# Qwiic_Relay_v11.net
KiCad netlist of a schematic drawn in EAGLE
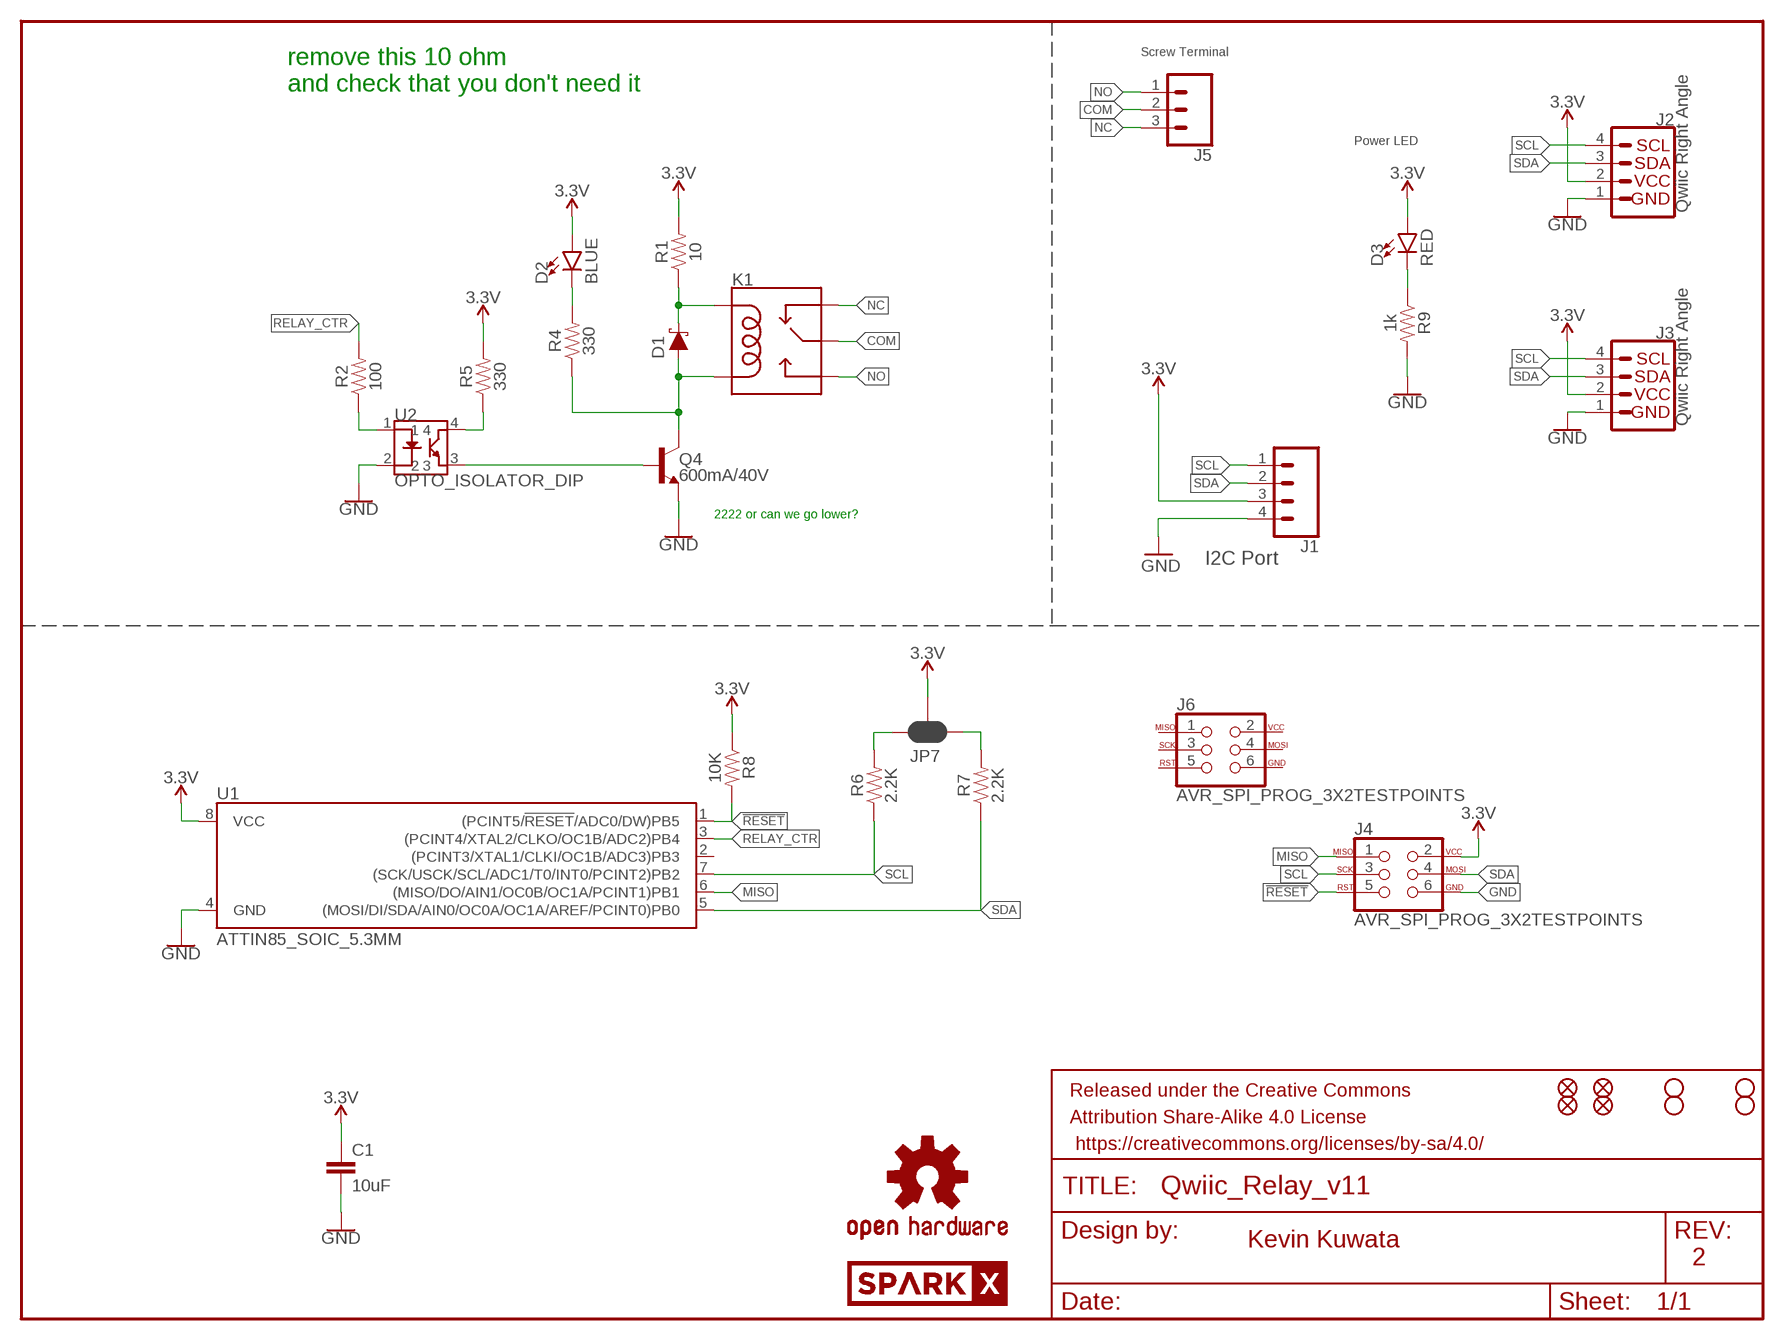
[diagram p0: schematic, sheet 1]

(export (version "E")
  (design (tool "Eeschema 10.0.6"))
  (components
    (comp (ref "C1")
      (value "10uF")
      (footprint "eagle-import:0603")
      (libsource (lib "eagle-import") (part "10UF-0603-6.3V-20%"))
    )
    (comp (ref "D1")
      (value "1A/23V/620mV")
      (footprint "eagle-import:SOD-323")
      (libsource (lib "eagle-import") (part "DIODE-SCHOTTKY-BAT20J"))
    )
    (comp (ref "D2")
      (value "BLUE")
      (footprint "eagle-import:LED-0603")
      (libsource (lib "eagle-import") (part "LED-BLUE0603"))
    )
    (comp (ref "D3")
      (value "RED")
      (footprint "eagle-import:LED-0603")
      (libsource (lib "eagle-import") (part "LED-RED0603"))
    )
    (comp (ref "FRAME1")
      (value "FRAME-LETTER")
      (footprint "eagle-import:CREATIVE_COMMONS")
      (libsource (lib "eagle-import") (part "FRAME-LETTER"))
    )
    (comp (ref "J1")
      (value "CONN_041X04_NO_SILK")
      (footprint "eagle-import:1X04_NO_SILK")
      (libsource (lib "eagle-import") (part "CONN_041X04_NO_SILK"))
    )
    (comp (ref "J2")
      (value "Qwiic Right Angle")
      (footprint "eagle-import:1X04_1MM_RA")
      (libsource (lib "eagle-import") (part "I2C_STANDARDQWIIC"))
    )
    (comp (ref "J3")
      (value "Qwiic Right Angle")
      (footprint "eagle-import:1X04_1MM_RA")
      (libsource (lib "eagle-import") (part "I2C_STANDARDQWIIC"))
    )
    (comp (ref "J4")
      (value "AVR_SPI_PROG_3X2TESTPOINTS")
      (footprint "eagle-import:2X3_TEST_POINTS")
      (libsource (lib "eagle-import") (part "AVR_SPI_PROG_3X2TESTPOINTS"))
    )
    (comp (ref "J5")
      (value "CONN_03-SCREW-5MM")
      (footprint "eagle-import:SCREWTERMINAL-5MM-3")
      (libsource (lib "eagle-import") (part "CONN_03-SCREW-5MM"))
    )
    (comp (ref "J6")
      (value "AVR_SPI_PROG_3X2TESTPOINTS")
      (footprint "eagle-import:2X3_TEST_POINTS")
      (libsource (lib "eagle-import") (part "AVR_SPI_PROG_3X2TESTPOINTS"))
    )
    (comp (ref "JP1")
      (value "STAND-OFF")
      (footprint "eagle-import:STAND-OFF")
      (libsource (lib "eagle-import") (part "STAND-OFF"))
    )
    (comp (ref "JP2")
      (value "FIDUCIALUFIDUCIAL")
      (footprint "eagle-import:MICRO-FIDUCIAL")
      (libsource (lib "eagle-import") (part "FIDUCIALUFIDUCIAL"))
    )
    (comp (ref "JP3")
      (value "STAND-OFF")
      (footprint "eagle-import:STAND-OFF")
      (libsource (lib "eagle-import") (part "STAND-OFF"))
    )
    (comp (ref "JP4")
      (value "STAND-OFF")
      (footprint "eagle-import:STAND-OFF")
      (libsource (lib "eagle-import") (part "STAND-OFF"))
    )
    (comp (ref "JP5")
      (value "STAND-OFF")
      (footprint "eagle-import:STAND-OFF")
      (libsource (lib "eagle-import") (part "STAND-OFF"))
    )
    (comp (ref "JP6")
      (value "FIDUCIALUFIDUCIAL")
      (footprint "eagle-import:MICRO-FIDUCIAL")
      (libsource (lib "eagle-import") (part "FIDUCIALUFIDUCIAL"))
    )
    (comp (ref "JP7")
      (value "JUMPER-SMT_3_2-NC_PASTE_SILK")
      (footprint "eagle-import:SMT-JUMPER_3_2-NC_PASTE_SILK")
      (libsource (lib "eagle-import") (part "JUMPER-SMT_3_2-NC_PASTE_SILK"))
    )
    (comp (ref "JP8")
      (value "FIDUCIALUFIDUCIAL")
      (footprint "eagle-import:MICRO-FIDUCIAL")
      (libsource (lib "eagle-import") (part "FIDUCIALUFIDUCIAL"))
    )
    (comp (ref "JP9")
      (value "FIDUCIALUFIDUCIAL")
      (footprint "eagle-import:MICRO-FIDUCIAL")
      (libsource (lib "eagle-import") (part "FIDUCIALUFIDUCIAL"))
    )
    (comp (ref "K1")
      (value "RELAY_SPDT_1C")
      (footprint "eagle-import:RELAY_SPDT_1C")
      (libsource (lib "eagle-import") (part "RELAY_SPDT_1C"))
    )
    (comp (ref "LOGO1")
      (value "OSHW-LOGOMINI")
      (footprint "eagle-import:OSHW-LOGO-MINI")
      (libsource (lib "eagle-import") (part "OSHW-LOGOMINI"))
    )
    (comp (ref "Q4")
      (value "600mA/40V")
      (footprint "eagle-import:SOT23-3")
      (libsource (lib "eagle-import") (part "TRANS_NPN-MMBT2222AL"))
    )
    (comp (ref "R1")
      (value "10")
      (footprint "eagle-import:0603")
      (libsource (lib "eagle-import") (part "47KOHM-0603-1/10W-1%"))
    )
    (comp (ref "R2")
      (value "100")
      (footprint "eagle-import:0603")
      (libsource (lib "eagle-import") (part "100OHM-0603-1/4W-5%"))
    )
    (comp (ref "R4")
      (value "330")
      (footprint "eagle-import:0603")
      (libsource (lib "eagle-import") (part "300OHM-0603-1/10W-1%"))
    )
    (comp (ref "R5")
      (value "330")
      (footprint "eagle-import:0603")
      (libsource (lib "eagle-import") (part "330OHM-0603-1/10W-1%"))
    )
    (comp (ref "R6")
      (value "2.2K")
      (footprint "eagle-import:0603")
      (libsource (lib "eagle-import") (part "4.7KOHM-0603-1/10W-1%"))
    )
    (comp (ref "R7")
      (value "2.2K")
      (footprint "eagle-import:0603")
      (libsource (lib "eagle-import") (part "4.7KOHM-0603-1/10W-1%"))
    )
    (comp (ref "R8")
      (value "10K")
      (footprint "eagle-import:0603")
      (libsource (lib "eagle-import") (part "330OHM-0603-1/10W-1%"))
    )
    (comp (ref "R9")
      (value "1k")
      (footprint "eagle-import:0603")
      (libsource (lib "eagle-import") (part "330OHM-0603-1/10W-1%"))
    )
    (comp (ref "U$3")
      (value "SPARKX-LOGO4")
      (footprint "eagle-import:SPARKX-MEDIUM")
      (libsource (lib "eagle-import") (part "SPARKX-LOGO4"))
    )
    (comp (ref "U$4")
      (value "SPARKX-LOGO4")
      (footprint "eagle-import:SPARKX-MEDIUM")
      (libsource (lib "eagle-import") (part "SPARKX-LOGO4"))
    )
    (comp (ref "U1")
      (value "ATTIN85_SOIC_5.3MM")
      (footprint "eagle-import:ATTINY85")
      (libsource (lib "eagle-import") (part "ATTIN85_SOIC_5.3MM"))
    )
    (comp (ref "U2")
      (value "OPTO_ISOLATOR_DIP")
      (footprint "eagle-import:4PIN_DIP")
      (libsource (lib "eagle-import") (part "OPTO_ISOLATOR_DIP"))
    )
  )
  (nets
    (net (code "1") (name "/~{RESET}") (class "Default")
      (node (ref "J4") (pin "5") (pinfunction "5_5") (pintype "passive"))
      (node (ref "R8") (pin "2") (pinfunction "2_2") (pintype "passive"))
      (node (ref "U1") (pin "1") (pinfunction "(PCINT5/~{RESET}/ADC0/DW)PB5_1") (pintype "bidirectional"))
    )
    (net (code "2") (name "3.3V") (class "Default")
      (node (ref "C1") (pin "1") (pinfunction "1_1") (pintype "passive"))
      (node (ref "D2") (pin "A") (pinfunction "A_A") (pintype "passive"))
      (node (ref "D3") (pin "A") (pinfunction "A_A") (pintype "passive"))
      (node (ref "J1") (pin "3") (pinfunction "3_3") (pintype "passive"))
      (node (ref "J2") (pin "2") (pinfunction "2_2") (pintype "power_in"))
      (node (ref "J3") (pin "2") (pinfunction "2_2") (pintype "power_in"))
      (node (ref "J4") (pin "2") (pinfunction "2_2") (pintype "passive"))
      (node (ref "JP7") (pin "2") (pinfunction "2_2") (pintype "passive"))
      (node (ref "R1") (pin "2") (pinfunction "2_2") (pintype "passive"))
      (node (ref "R5") (pin "2") (pinfunction "2_2") (pintype "passive"))
      (node (ref "R8") (pin "1") (pinfunction "1_1") (pintype "passive"))
      (node (ref "U1") (pin "8") (pinfunction "VCC_8") (pintype "bidirectional"))
    )
    (net (code "3") (name "COM") (class "Default")
      (node (ref "J5") (pin "2") (pinfunction "2_2") (pintype "passive"))
      (node (ref "K1") (pin "1") (pinfunction "MAIN_1") (pintype "bidirectional"))
    )
    (net (code "4") (name "GND") (class "Default")
      (node (ref "C1") (pin "2") (pinfunction "2_2") (pintype "passive"))
      (node (ref "J1") (pin "4") (pinfunction "4_4") (pintype "passive"))
      (node (ref "J2") (pin "1") (pinfunction "1_1") (pintype "power_in"))
      (node (ref "J3") (pin "1") (pinfunction "1_1") (pintype "power_in"))
      (node (ref "J4") (pin "6") (pinfunction "6_6") (pintype "passive"))
      (node (ref "Q4") (pin "2") (pinfunction "E_2") (pintype "passive"))
      (node (ref "R9") (pin "2") (pinfunction "2_2") (pintype "passive"))
      (node (ref "U1") (pin "4") (pinfunction "GND_4") (pintype "bidirectional"))
      (node (ref "U2") (pin "2") (pinfunction "2_2") (pintype "bidirectional"))
    )
    (net (code "5") (name "MISO") (class "Default")
      (node (ref "J4") (pin "1") (pinfunction "1_1") (pintype "passive"))
      (node (ref "U1") (pin "6") (pinfunction "(MISO/DO/AIN1/OC0B/OC1A/PCINT1)PB1_6") (pintype "bidirectional"))
    )
    (net (code "6") (name "NC") (class "Default")
      (node (ref "J5") (pin "3") (pinfunction "3_3") (pintype "passive"))
      (node (ref "K1") (pin "4") (pinfunction "NC_4") (pintype "bidirectional"))
    )
    (net (code "7") (name "NO") (class "Default")
      (node (ref "J5") (pin "1") (pinfunction "1_1") (pintype "passive"))
      (node (ref "K1") (pin "3") (pinfunction "NO_3") (pintype "bidirectional"))
    )
    (net (code "8") (name "Net-(D2-PadC)") (class "Default")
      (node (ref "D2") (pin "C") (pinfunction "C_C") (pintype "passive"))
      (node (ref "R4") (pin "2") (pinfunction "2_2") (pintype "passive"))
    )
    (net (code "9") (name "Net-(D3-PadC)") (class "Default")
      (node (ref "D3") (pin "C") (pinfunction "C_C") (pintype "passive"))
      (node (ref "R9") (pin "1") (pinfunction "1_1") (pintype "passive"))
    )
    (net (code "10") (name "Net-(JP7-Pad1)") (class "Default")
      (node (ref "JP7") (pin "1") (pinfunction "1_1") (pintype "passive"))
      (node (ref "R7") (pin "2") (pinfunction "2_2") (pintype "passive"))
    )
    (net (code "11") (name "Net-(JP7-Pad3)") (class "Default")
      (node (ref "JP7") (pin "3") (pinfunction "3_3") (pintype "passive"))
      (node (ref "R6") (pin "2") (pinfunction "2_2") (pintype "passive"))
    )
    (net (code "12") (name "Net-(K1-COIL1)") (class "Default")
      (node (ref "D1") (pin "C") (pinfunction "C_C") (pintype "passive"))
      (node (ref "K1") (pin "2") (pinfunction "COIL1_2") (pintype "bidirectional"))
      (node (ref "R1") (pin "1") (pinfunction "1_1") (pintype "passive"))
    )
    (net (code "13") (name "Net-(K1-COIL2)") (class "Default")
      (node (ref "D1") (pin "A") (pinfunction "A_A") (pintype "passive"))
      (node (ref "K1") (pin "5") (pinfunction "COIL2_5") (pintype "bidirectional"))
      (node (ref "Q4") (pin "3") (pinfunction "C_3") (pintype "passive"))
      (node (ref "R4") (pin "1") (pinfunction "1_1") (pintype "passive"))
    )
    (net (code "14") (name "Net-(Q4-B)") (class "Default")
      (node (ref "Q4") (pin "1") (pinfunction "B_1") (pintype "passive"))
      (node (ref "U2") (pin "3") (pinfunction "3_3") (pintype "bidirectional"))
    )
    (net (code "15") (name "Net-(R2-Pad1)") (class "Default")
      (node (ref "R2") (pin "1") (pinfunction "1_1") (pintype "passive"))
      (node (ref "U2") (pin "1") (pinfunction "1_1") (pintype "bidirectional"))
    )
    (net (code "16") (name "Net-(R5-Pad1)") (class "Default")
      (node (ref "R5") (pin "1") (pinfunction "1_1") (pintype "passive"))
      (node (ref "U2") (pin "4") (pinfunction "4_4") (pintype "bidirectional"))
    )
    (net (code "17") (name "RELAY_CTR") (class "Default")
      (node (ref "R2") (pin "2") (pinfunction "2_2") (pintype "passive"))
      (node (ref "U1") (pin "3") (pinfunction "(PCINT4/XTAL2/CLKO/OC1B/ADC2)PB4_3") (pintype "bidirectional"))
    )
    (net (code "18") (name "SCL") (class "Default")
      (node (ref "J1") (pin "1") (pinfunction "1_1") (pintype "passive"))
      (node (ref "J2") (pin "4") (pinfunction "4_4") (pintype "passive"))
      (node (ref "J3") (pin "4") (pinfunction "4_4") (pintype "passive"))
      (node (ref "J4") (pin "3") (pinfunction "3_3") (pintype "passive"))
      (node (ref "R6") (pin "1") (pinfunction "1_1") (pintype "passive"))
      (node (ref "U1") (pin "7") (pinfunction "(SCK/USCK/SCL/ADC1/T0/INT0/PCINT2)PB2_7") (pintype "bidirectional"))
    )
    (net (code "19") (name "SDA") (class "Default")
      (node (ref "J1") (pin "2") (pinfunction "2_2") (pintype "passive"))
      (node (ref "J2") (pin "3") (pinfunction "3_3") (pintype "passive"))
      (node (ref "J3") (pin "3") (pinfunction "3_3") (pintype "passive"))
      (node (ref "J4") (pin "4") (pinfunction "4_4") (pintype "passive"))
      (node (ref "R7") (pin "1") (pinfunction "1_1") (pintype "passive"))
      (node (ref "U1") (pin "5") (pinfunction "(MOSI/DI/SDA/AIN0/OC0A/OC1A/AREF/PCINT0)PB0_5") (pintype "bidirectional"))
    )
    (net (code "20") (name "unconnected-(J6-Pad1)") (class "Default")
      (node (ref "J6") (pin "1") (pinfunction "1_1") (pintype "passive"))
    )
    (net (code "21") (name "unconnected-(J6-Pad2)") (class "Default")
      (node (ref "J6") (pin "2") (pinfunction "2_2") (pintype "passive"))
    )
    (net (code "22") (name "unconnected-(J6-Pad3)") (class "Default")
      (node (ref "J6") (pin "3") (pinfunction "3_3") (pintype "passive"))
    )
    (net (code "23") (name "unconnected-(J6-Pad4)") (class "Default")
      (node (ref "J6") (pin "4") (pinfunction "4_4") (pintype "passive"))
    )
    (net (code "24") (name "unconnected-(J6-Pad5)") (class "Default")
      (node (ref "J6") (pin "5") (pinfunction "5_5") (pintype "passive"))
    )
    (net (code "25") (name "unconnected-(J6-Pad6)") (class "Default")
      (node (ref "J6") (pin "6") (pinfunction "6_6") (pintype "passive"))
    )
    (net (code "26") (name "unconnected-(U1-(PCINT3{slash}XTAL1{slash}CLKI{slash}OC1B{slash}ADC3)PB3-Pad2)") (class "Default")
      (node (ref "U1") (pin "2") (pinfunction "(PCINT3/XTAL1/CLKI/OC1B/ADC3)PB3_2") (pintype "bidirectional"))
    )
  )
)
